# Sheet2.net
KiCad netlist of a schematic drawn in Altium Designer
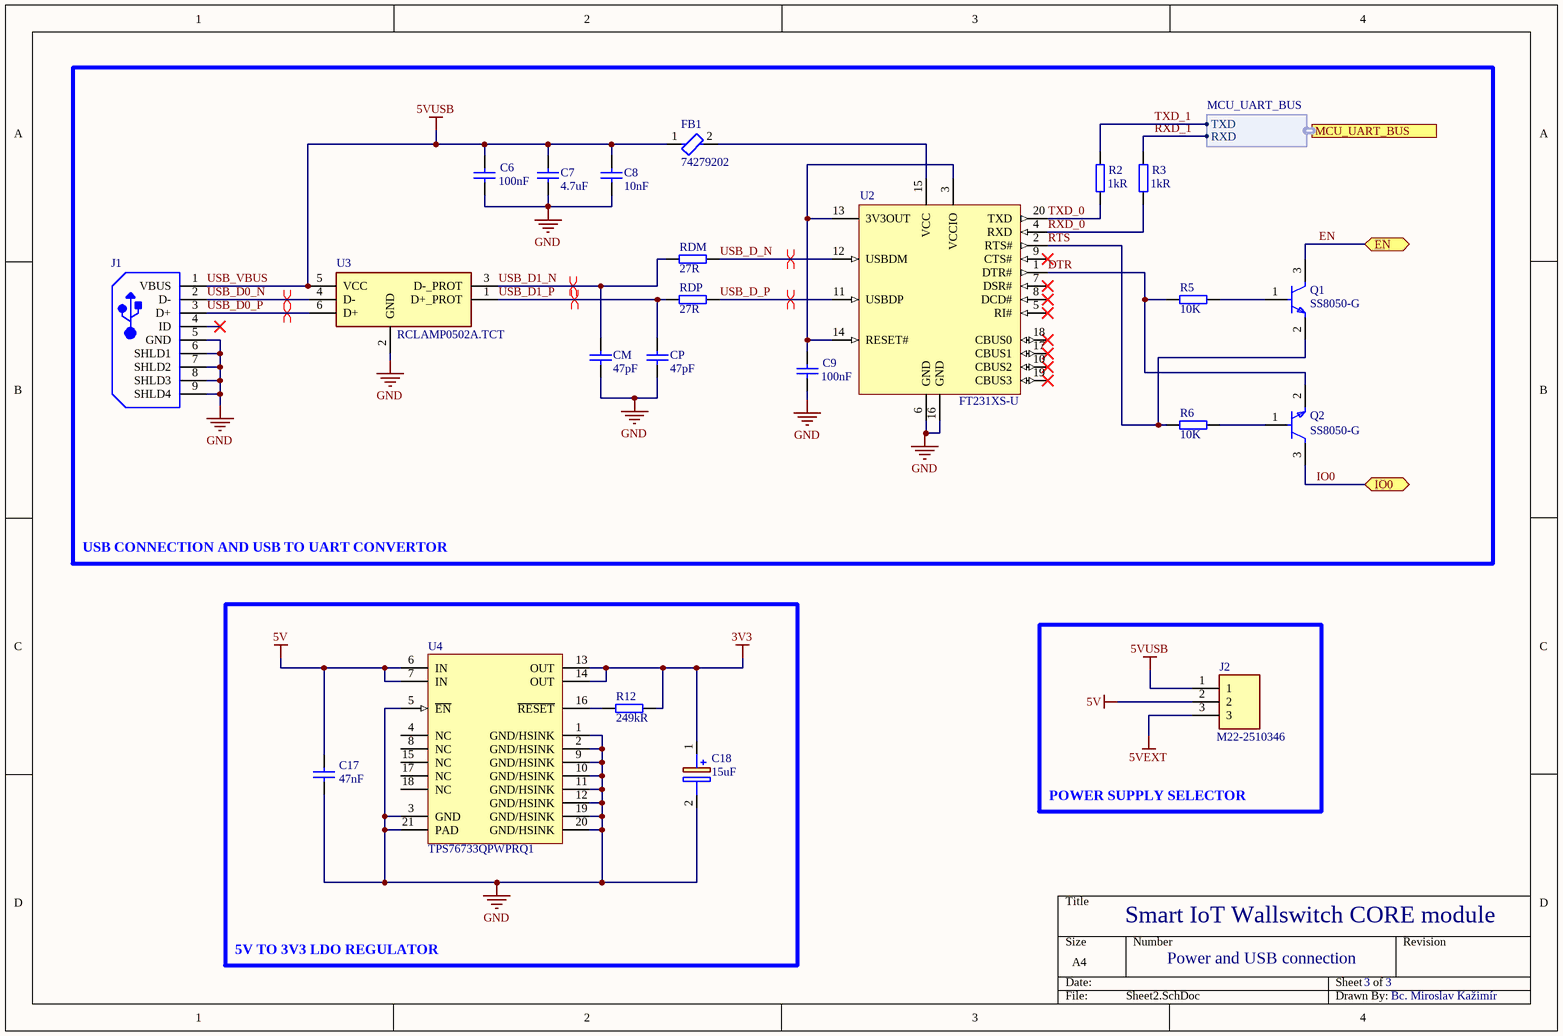
[diagram p0: Sheet2.SchDoc]

(export (version "E")
  (design (tool "Eeschema 10.0.6"))
  (components
    (comp (ref "C6")
      (value "C0805C104K5RAC7411")
      (footprint "FP-C0805C-DN-IPC_A")
      (description "Cap Ceramic 0.1uF 50V X7R 10% SMD 0805 125°C Paper T/R")
      (fields
        (field (name "MANUFACTURER") "KEMET")
        (field (name "TOLERANCE") "10%")
        (field (name "CAPACITANCE") "100nF")
      )
      (libsource (lib "Schlib1") (part "C0805C104K5RAC7411"))
    )
    (comp (ref "C7")
      (value "GRM21BR71C475KE51L")
      (footprint "FP-GRM21B-0_15-IPC_A")
      (description "Cap Ceramic 4.7uF 16V X7R 10% SMD 0805 125°C Embossed Plastic T/R")
      (fields
        (field (name "MANUFACTURER") "Murata")
        (field (name "CAPACITANCE") "4.7uF")
        (field (name "TOLERANCE") "10%")
      )
      (libsource (lib "Schlib1") (part "GRM21BR71C475KE51L"))
    )
    (comp (ref "C8")
      (value "C0805C103J5RAC7025")
      (footprint "FP-C0805C-DN-IPC_A")
      (description "Cap Ceramic 0.01uF 50V X7R 5% SMD 0805 125°C Paper T/R")
      (fields
        (field (name "MANUFACTURER") "KEMET")
        (field (name "CAPACITANCE") "10nF")
        (field (name "TOLERANCE") "5%")
      )
      (libsource (lib "Schlib1") (part "C0805C103J5RAC7025"))
    )
    (comp (ref "C9")
      (value "C0805C104K5RAC7411")
      (footprint "FP-C0805C-DN-IPC_A")
      (description "Cap Ceramic 0.1uF 50V X7R 10% SMD 0805 125°C Paper T/R")
      (fields
        (field (name "MANUFACTURER") "KEMET")
        (field (name "TOLERANCE") "10%")
        (field (name "CAPACITANCE") "100nF")
      )
      (libsource (lib "Schlib1") (part "C0805C104K5RAC7411"))
    )
    (comp (ref "C17")
      (value "C0805C473K5RACAUTO")
      (footprint "FP-C0805C-DN-IPC_A")
      (fields
        (field (name "MANUFACTURER") "KEMET")
        (field (name "CAPACITANCE") "47nF")
        (field (name "TOLERANCE") "10%")
      )
      (libsource (lib "Schlib1") (part "C0805C473K5RACAUTO"))
    )
    (comp (ref "C18")
      (value "T495A156K010ATE1K0")
      (footprint "CAPPM3216X180N")
      (fields
        (field (name "MANUFACTURER") "KEMET")
        (field (name "CAPACITANCE") "15uF")
        (field (name "TOLERANCE") "10%")
      )
      (libsource (lib "Schlib1") (part "T495A156K010ATE1K0"))
    )
    (comp (ref "CM")
      (value "C0805C470J5RACTU")
      (footprint "FP-C0805C-DN-IPC_A")
      (description "47.0Pf 50.0V Rohs Compliant: Yes")
      (fields (field (name "MANUFACTURER") "KEMET") (field (name "CAPACITANCE") "47pF"))
      (libsource (lib "Schlib1") (part "C0805C470J5RACTU"))
    )
    (comp (ref "CP")
      (value "C0805C470J5RACTU")
      (footprint "FP-C0805C-DN-IPC_A")
      (description "47.0Pf 50.0V Rohs Compliant: Yes")
      (fields (field (name "MANUFACTURER") "KEMET") (field (name "CAPACITANCE") "47pF"))
      (libsource (lib "Schlib1") (part "C0805C470J5RACTU"))
    )
    (comp (ref "FB1")
      (value "74279202")
      (footprint "SMD-0805")
      (description "Ferrite SMD Construction form: 0805 DC resistance: 0.1 Ohm Impedance @ 100 MHz: 120 Ohm")
      (fields (field (name "MANUFACTURER") "Wurth Electronics") (field (name "TOLERANCE") "25%"))
      (libsource (lib "Schlib1") (part "74279202"))
    )
    (comp (ref "J1")
      (value "10104110-0001LF")
      (footprint "101041100001LF")
      (description "Conn Micro USB 2.0 Type B RCP 5 POS 0.65mm Solder RA SMD 5 Terminal 1 Port T/R")
      (fields (field (name "MANUFACTURER") "Amphenol ICC / FCI"))
      (libsource (lib "Schlib1") (part "10104110-0001LF"))
    )
    (comp (ref "J2")
      (value "M22-2510346")
      (footprint "HDRV3W50P0X200_1X3_600X200X525P")
      (fields (field (name "MANUFACTURER") "Harwin"))
      (libsource (lib "Schlib1") (part "M22-2510346"))
    )
    (comp (ref "Q1")
      (value "SS8050-G")
      (footprint "FP-SS8050-G-IPC_A")
      (description "Trans Gp Bjt NPN 25V 1.5A 300MW 3-PIN SOT-23 T/r")
      (fields (field (name "MANUFACTURER") "Comchip"))
      (libsource (lib "Schlib1") (part "SS8050-G"))
    )
    (comp (ref "Q2")
      (value "SS8050-G")
      (footprint "FP-SS8050-G-IPC_A")
      (description "Trans Gp Bjt NPN 25V 1.5A 300MW 3-PIN SOT-23 T/r")
      (fields (field (name "MANUFACTURER") "Comchip"))
      (libsource (lib "Schlib1") (part "SS8050-G"))
    )
    (comp (ref "R2")
      (value "ERJ-3GEYJ102V")
      (footprint "FP-ERJ3G-IPC_A")
      (description "RES SMD 1K OHM 5% 1/10W 0603")
      (fields
        (field (name "MANUFACTURER") "Panasonic")
        (field (name "RESISTANCE") "1kR")
        (field (name "TOLERANCE") "5%")
      )
      (libsource (lib "Schlib1") (part "ERJ-3GEYJ102V"))
    )
    (comp (ref "R3")
      (value "ERJ-3GEYJ102V")
      (footprint "FP-ERJ3G-IPC_A")
      (description "RES SMD 1K OHM 5% 1/10W 0603")
      (fields
        (field (name "MANUFACTURER") "Panasonic")
        (field (name "RESISTANCE") "1kR")
        (field (name "TOLERANCE") "5%")
      )
      (libsource (lib "Schlib1") (part "ERJ-3GEYJ102V"))
    )
    (comp (ref "R5")
      (value "ERJ-UP6J103V")
      (footprint "RESC2012X70N")
      (description "Res 10K Ohm 5% 1/2W 0805")
      (fields (field (name "MANUFACTURER") "Panasonic") (field (name "RESISTANCE") "10K"))
      (libsource (lib "Schlib1") (part "ERJ-UP6J103V"))
    )
    (comp (ref "R6")
      (value "ERJ-UP6J103V")
      (footprint "RESC2012X70N")
      (description "Res 10K Ohm 5% 1/2W 0805")
      (fields (field (name "MANUFACTURER") "Panasonic") (field (name "RESISTANCE") "10K"))
      (libsource (lib "Schlib1") (part "ERJ-UP6J103V"))
    )
    (comp (ref "R12")
      (value "ERJ-6ENF2493V")
      (footprint "RESC2013X70X40NL20T20")
      (description "Res Thick Film 0805 249K Ohm 1% 1/8W ±100ppm/°C Molded SMD Punched Carrier T/R")
      (fields
        (field (name "MANUFACTURER") "Panasonic")
        (field (name "RESISTANCE") "249kR")
        (field (name "TOLERANCE") "1%")
      )
      (libsource (lib "Schlib1") (part "ERJ-6ENF2493V"))
    )
    (comp (ref "RDM")
      (value "ERJ-P06F27R0V")
      (footprint "RES_ERJP06F27R0V")
      (description "Res Thick Film 0805 27 Ohm 1% 0.25W ±300ppm/°C Molded SMD Punched Carrier T/R")
      (fields
        (field (name "MANUFACTURER") "Panasonic")
        (field (name "RESISTANCE") "27R")
        (field (name "TOLERANCE") "1%")
      )
      (libsource (lib "Schlib1") (part "ERJ-P06F27R0V"))
    )
    (comp (ref "RDP")
      (value "ERJ-P06F27R0V")
      (footprint "RES_ERJP06F27R0V")
      (description "Res Thick Film 0805 27 Ohm 1% 0.25W ±300ppm/°C Molded SMD Punched Carrier T/R")
      (fields
        (field (name "MANUFACTURER") "Panasonic")
        (field (name "RESISTANCE") "27R")
        (field (name "TOLERANCE") "1%")
      )
      (libsource (lib "Schlib1") (part "ERJ-P06F27R0V"))
    )
    (comp (ref "U2")
      (value "FT231XS-U")
      (footprint "SSOP-20_L")
      (description "FT231XS-U, Usb Controller, 3MBD, Usb 1.1, Usb 2.0, 5 V, 20-PIN SSOP")
      (fields (field (name "MANUFACTURER") "FTDI"))
      (libsource (lib "Schlib1") (part "FT231XS-U"))
    )
    (comp (ref "U3")
      (value "RCLAMP0502A.TCT")
      (footprint "SOTFL50P162X60-6N")
      (description "TVS二极管 5V IPPM=3A 50W 单向")
      (fields (field (name "MANUFACTURER") "Semtech") (field (name "VOLTAGE") "5V"))
      (libsource (lib "Schlib1") (part "RCLAMP0502A.TCT"))
    )
    (comp (ref "U4")
      (value "TPS76733QPWPRQ1")
      (footprint "PWP0020L_L")
      (description "Automotive 1-A, 10-V, low-dropout voltage regulator with enable 20-HTSSOP -40 to 125")
      (fields (field (name "MANUFACTURER") "Texas Instruments"))
      (libsource (lib "Schlib1") (part "TPS76733QPWPRQ1"))
    )
  )
  (nets
    (net (code "2") (name "/DTR") (class "Default")
      (node (ref "Q2") (pin "2") (pinfunction "E_2") (pintype "passive"))
      (node (ref "R5") (pin "1") (pinfunction "1_1") (pintype "passive"))
      (node (ref "U2") (pin "1") (pinfunction "DTR#_1") (pintype "output"))
    )
    (net (code "3") (name "/EN") (class "Default")
      (node (ref "Q1") (pin "3") (pinfunction "C_3") (pintype "passive"))
    )
    (net (code "4") (name "/IO0") (class "Default")
      (node (ref "Q2") (pin "3") (pinfunction "C_3") (pintype "passive"))
    )
    (net (code "5") (name "/RTS") (class "Default")
      (node (ref "Q1") (pin "2") (pinfunction "E_2") (pintype "passive"))
      (node (ref "R6") (pin "1") (pinfunction "1_1") (pintype "passive"))
      (node (ref "U2") (pin "2") (pinfunction "RTS#_2") (pintype "output"))
    )
    (net (code "6") (name "/RXD_0") (class "Default")
      (node (ref "R3") (pin "2") (pinfunction "2_2") (pintype "passive"))
      (node (ref "U2") (pin "4") (pinfunction "RXD_4") (pintype "input"))
    )
    (net (code "7") (name "/RXD_1") (class "Default")
      (node (ref "R3") (pin "1") (pinfunction "1_1") (pintype "passive"))
    )
    (net (code "8") (name "/TXD_0") (class "Default")
      (node (ref "R2") (pin "2") (pinfunction "2_2") (pintype "passive"))
      (node (ref "U2") (pin "20") (pinfunction "TXD_20") (pintype "output"))
    )
    (net (code "9") (name "/TXD_1") (class "Default")
      (node (ref "R2") (pin "1") (pinfunction "1_1") (pintype "passive"))
    )
    (net (code "10") (name "/USB_D0_N") (class "Default")
      (node (ref "J1") (pin "2") (pinfunction "D-_2") (pintype "passive"))
      (node (ref "U3") (pin "4") (pinfunction "D-_4") (pintype "passive"))
    )
    (net (code "11") (name "/USB_D0_P") (class "Default")
      (node (ref "J1") (pin "3") (pinfunction "D+_3") (pintype "passive"))
      (node (ref "U3") (pin "6") (pinfunction "D+_6") (pintype "passive"))
    )
    (net (code "12") (name "/USB_D1_N") (class "Default")
      (node (ref "CM") (pin "1") (pinfunction "1_1") (pintype "passive"))
      (node (ref "RDM") (pin "1") (pinfunction "1_1") (pintype "passive"))
      (node (ref "U3") (pin "3") (pinfunction "D-_PROT_3") (pintype "passive"))
    )
    (net (code "13") (name "/USB_D1_P") (class "Default")
      (node (ref "CP") (pin "1") (pinfunction "1_1") (pintype "passive"))
      (node (ref "RDP") (pin "1") (pinfunction "1_1") (pintype "passive"))
      (node (ref "U3") (pin "1") (pinfunction "D+_PROT_1") (pintype "passive"))
    )
    (net (code "14") (name "/USB_D_N") (class "Default")
      (node (ref "RDM") (pin "2") (pinfunction "2_2") (pintype "passive"))
      (node (ref "U2") (pin "12") (pinfunction "USBDM_12") (pintype "input"))
    )
    (net (code "15") (name "/USB_D_P") (class "Default")
      (node (ref "RDP") (pin "2") (pinfunction "2_2") (pintype "passive"))
      (node (ref "U2") (pin "11") (pinfunction "USBDP_11") (pintype "input"))
    )
    (net (code "17") (name "3V3") (class "Default")
      (node (ref "C18") (pin "1") (pinfunction "+_1") (pintype "passive"))
      (node (ref "R12") (pin "1") (pinfunction "1_1") (pintype "passive"))
      (node (ref "U4") (pin "13") (pinfunction "OUT_13") (pintype "power_in"))
      (node (ref "U4") (pin "14") (pinfunction "OUT_14") (pintype "power_in"))
    )
    (net (code "18") (name "5V") (class "Default")
      (node (ref "C17") (pin "1") (pinfunction "1_1") (pintype "passive"))
      (node (ref "J2") (pin "2") (pinfunction "2_2") (pintype "passive"))
      (node (ref "U4") (pin "6") (pinfunction "IN_6") (pintype "power_in"))
      (node (ref "U4") (pin "7") (pinfunction "IN_7") (pintype "power_in"))
    )
    (net (code "19") (name "5VEXT") (class "Default")
      (node (ref "J2") (pin "3") (pinfunction "3_3") (pintype "passive"))
    )
    (net (code "20") (name "5VUSB") (class "Default")
      (node (ref "C6") (pin "1") (pinfunction "1_1") (pintype "passive"))
      (node (ref "C7") (pin "1") (pinfunction "1_1") (pintype "passive"))
      (node (ref "C8") (pin "1") (pinfunction "1_1") (pintype "passive"))
      (node (ref "FB1") (pin "1") (pinfunction "1_1") (pintype "passive"))
      (node (ref "J1") (pin "1") (pinfunction "VBUS_1") (pintype "power_in"))
      (node (ref "J2") (pin "1") (pinfunction "1_1") (pintype "passive"))
      (node (ref "U3") (pin "5") (pinfunction "VCC_5") (pintype "passive"))
    )
    (net (code "21") (name "GND") (class "Default")
      (node (ref "C17") (pin "2") (pinfunction "2_2") (pintype "passive"))
      (node (ref "C18") (pin "2") (pinfunction "-_2") (pintype "passive"))
      (node (ref "C6") (pin "2") (pinfunction "2_2") (pintype "passive"))
      (node (ref "C7") (pin "2") (pinfunction "2_2") (pintype "passive"))
      (node (ref "C8") (pin "2") (pinfunction "2_2") (pintype "passive"))
      (node (ref "C9") (pin "2") (pinfunction "2_2") (pintype "passive"))
      (node (ref "CM") (pin "2") (pinfunction "2_2") (pintype "passive"))
      (node (ref "CP") (pin "2") (pinfunction "2_2") (pintype "passive"))
      (node (ref "J1") (pin "5") (pinfunction "GND_5") (pintype "power_in"))
      (node (ref "J1") (pin "6") (pinfunction "SHLD1_6") (pintype "passive"))
      (node (ref "J1") (pin "7") (pinfunction "SHLD2_7") (pintype "passive"))
      (node (ref "J1") (pin "8") (pinfunction "SHLD3_8") (pintype "passive"))
      (node (ref "J1") (pin "9") (pinfunction "SHLD4_9") (pintype "passive"))
      (node (ref "U2") (pin "16") (pinfunction "GND_16") (pintype "power_in"))
      (node (ref "U2") (pin "6") (pinfunction "GND_6") (pintype "power_in"))
      (node (ref "U3") (pin "2") (pinfunction "GND_2") (pintype "passive"))
      (node (ref "U4") (pin "1") (pinfunction "GND/HSINK_1") (pintype "power_in"))
      (node (ref "U4") (pin "10") (pinfunction "GND/HSINK_10") (pintype "power_in"))
      (node (ref "U4") (pin "11") (pinfunction "GND/HSINK_11") (pintype "power_in"))
      (node (ref "U4") (pin "12") (pinfunction "GND/HSINK_12") (pintype "power_in"))
      (node (ref "U4") (pin "19") (pinfunction "GND/HSINK_19") (pintype "power_in"))
      (node (ref "U4") (pin "2") (pinfunction "GND/HSINK_2") (pintype "power_in"))
      (node (ref "U4") (pin "20") (pinfunction "GND/HSINK_20") (pintype "power_in"))
      (node (ref "U4") (pin "21") (pinfunction "PAD_21") (pintype "passive"))
      (node (ref "U4") (pin "3") (pinfunction "GND_3") (pintype "power_in"))
      (node (ref "U4") (pin "5") (pinfunction "~{EN}_5") (pintype "input"))
      (node (ref "U4") (pin "9") (pinfunction "GND/HSINK_9") (pintype "power_in"))
    )
    (net (code "22") (name "Net-(Q1-B)") (class "Default")
      (node (ref "Q1") (pin "1") (pinfunction "B_1") (pintype "passive"))
      (node (ref "R5") (pin "2") (pinfunction "2_2") (pintype "passive"))
    )
    (net (code "23") (name "Net-(Q2-B)") (class "Default")
      (node (ref "Q2") (pin "1") (pinfunction "B_1") (pintype "passive"))
      (node (ref "R6") (pin "2") (pinfunction "2_2") (pintype "passive"))
    )
    (net (code "24") (name "Net-(U2-3V3OUT)") (class "Default")
      (node (ref "C9") (pin "1") (pinfunction "1_1") (pintype "passive"))
      (node (ref "U2") (pin "13") (pinfunction "3V3OUT_13") (pintype "power_in"))
      (node (ref "U2") (pin "14") (pinfunction "RESET#_14") (pintype "input"))
      (node (ref "U2") (pin "3") (pinfunction "VCCIO_3") (pintype "power_in"))
    )
    (net (code "25") (name "Net-(U2-VCC)") (class "Default")
      (node (ref "FB1") (pin "2") (pinfunction "2_2") (pintype "passive"))
      (node (ref "U2") (pin "15") (pinfunction "VCC_15") (pintype "power_in"))
    )
    (net (code "26") (name "Net-(U4-~{RESET})") (class "Default")
      (node (ref "R12") (pin "2") (pinfunction "2_2") (pintype "passive"))
      (node (ref "U4") (pin "16") (pinfunction "~{RESET}_16") (pintype "tri_state"))
    )
    (net (code "27") (name "unconnected-(J1-ID-Pad4)") (class "Default")
      (node (ref "J1") (pin "4") (pinfunction "ID_4") (pintype "passive+no_connect"))
    )
    (net (code "28") (name "unconnected-(U2-CBUS0-Pad18)") (class "Default")
      (node (ref "U2") (pin "18") (pinfunction "CBUS0_18") (pintype "bidirectional+no_connect"))
    )
    (net (code "29") (name "unconnected-(U2-CBUS1-Pad17)") (class "Default")
      (node (ref "U2") (pin "17") (pinfunction "CBUS1_17") (pintype "bidirectional+no_connect"))
    )
    (net (code "30") (name "unconnected-(U2-CBUS2-Pad10)") (class "Default")
      (node (ref "U2") (pin "10") (pinfunction "CBUS2_10") (pintype "bidirectional+no_connect"))
    )
    (net (code "31") (name "unconnected-(U2-CBUS3-Pad19)") (class "Default")
      (node (ref "U2") (pin "19") (pinfunction "CBUS3_19") (pintype "bidirectional+no_connect"))
    )
    (net (code "32") (name "unconnected-(U2-CTS#-Pad9)") (class "Default")
      (node (ref "U2") (pin "9") (pinfunction "CTS#_9") (pintype "input+no_connect"))
    )
    (net (code "33") (name "unconnected-(U2-DCD#-Pad8)") (class "Default")
      (node (ref "U2") (pin "8") (pinfunction "DCD#_8") (pintype "input+no_connect"))
    )
    (net (code "34") (name "unconnected-(U2-DSR#-Pad7)") (class "Default")
      (node (ref "U2") (pin "7") (pinfunction "DSR#_7") (pintype "input+no_connect"))
    )
    (net (code "35") (name "unconnected-(U2-RI#-Pad5)") (class "Default")
      (node (ref "U2") (pin "5") (pinfunction "RI#_5") (pintype "input+no_connect"))
    )
    (net (code "36") (name "unconnected-(U4-NC-Pad4)") (class "Default")
      (node (ref "U4") (pin "4") (pinfunction "NC_4") (pintype "passive"))
    )
    (net (code "37") (name "unconnected-(U4-NC-Pad8)") (class "Default")
      (node (ref "U4") (pin "8") (pinfunction "NC_8") (pintype "passive"))
    )
    (net (code "38") (name "unconnected-(U4-NC-Pad15)") (class "Default")
      (node (ref "U4") (pin "15") (pinfunction "NC_15") (pintype "passive"))
    )
    (net (code "39") (name "unconnected-(U4-NC-Pad17)") (class "Default")
      (node (ref "U4") (pin "17") (pinfunction "NC_17") (pintype "passive"))
    )
    (net (code "40") (name "unconnected-(U4-NC-Pad18)") (class "Default")
      (node (ref "U4") (pin "18") (pinfunction "NC_18") (pintype "passive"))
    )
  )
)
